# 12V_IdealDiode_PowerSupply_v1.net
KiCad netlist of a schematic drawn in Altium Designer
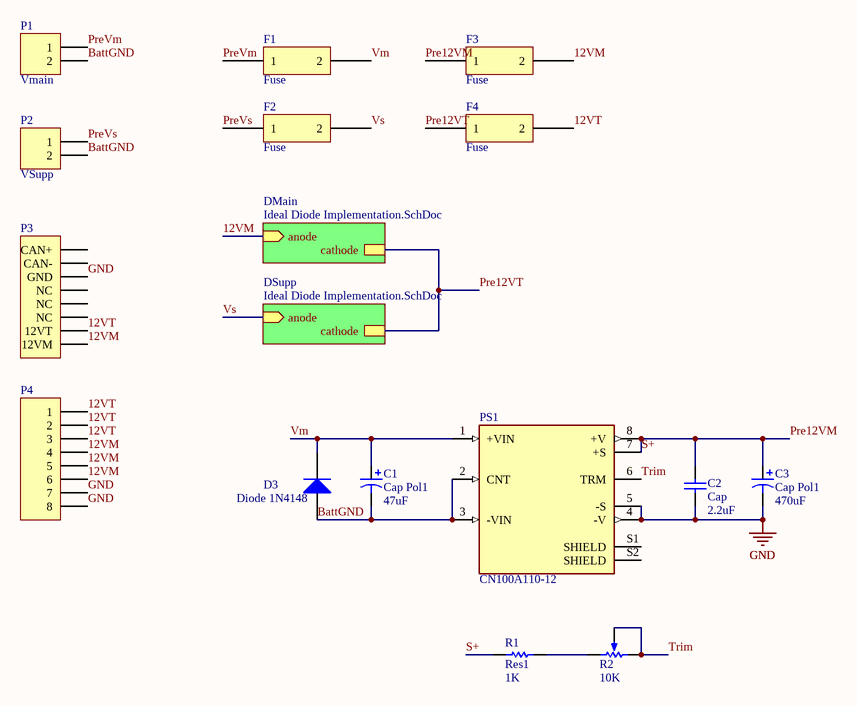
[diagram p0: 12V_IdealDiode_PowerSupply_v1.SchDoc]

(export (version "E")
  (design (tool "Eeschema 10.0.6"))
  (components
    (comp (ref "C1")
      (value "Cap Pol1")
      (footprint "RB7.6-15")
      (description "Polarized Capacitor (Radial)")
      (fields (field (name "ALTIUM_VALUE") "47uF") (field (name "PUBLISHER") "Altium Limited"))
      (libsource (lib "Miscellaneous Devices") (part "Cap Pol1"))
    )
    (comp (ref "C2")
      (value "Cap")
      (footprint "RAD-0.3")
      (description "Ceramic Capacitor")
      (fields (field (name "ALTIUM_VALUE") "2.2uF") (field (name "PUBLISHER") "Altium Limited"))
      (libsource (lib "Miscellaneous Devices") (part "Cap"))
    )
    (comp (ref "C3")
      (value "Cap Pol1")
      (footprint "RB7.6-15")
      (description "Polarized Capacitor (Radial)")
      (fields (field (name "ALTIUM_VALUE") "470uF") (field (name "PUBLISHER") "Altium Limited"))
      (libsource (lib "Miscellaneous Devices") (part "Cap Pol1"))
    )
    (comp (ref "D3")
      (value "Diode 1N4148")
      (footprint "DO-35")
      (description "High Conductance Fast Diode")
      (fields (field (name "PUBLISHER") "Altium Limited"))
      (libsource (lib "Miscellaneous Devices") (part "Diode 1N4148"))
    )
    (comp (ref "F1") (value "Fuse") (footprint "Fuse Hilder") (libsource (lib "SolarGators") (part "Fuse")))
    (comp (ref "F2") (value "Fuse") (footprint "Fuse Hilder") (libsource (lib "SolarGators") (part "Fuse")))
    (comp (ref "F3") (value "Fuse") (footprint "Fuse Hilder") (libsource (lib "SolarGators") (part "Fuse")))
    (comp (ref "F4") (value "Fuse") (footprint "Fuse Hilder") (libsource (lib "SolarGators") (part "Fuse")))
    (comp (ref "P1")
      (value "Vmain")
      (footprint "HDR1X2H")
      (description "Header, 2-Pin, Right Angle")
      (fields (field (name "PUBLISHER") "Altium Limited"))
      (libsource (lib "Miscellaneous Connectors") (part "Header 2H"))
    )
    (comp (ref "P2")
      (value "VSupp")
      (footprint "HDR1X2H")
      (description "Header, 2-Pin, Right Angle")
      (fields (field (name "PUBLISHER") "Altium Limited"))
      (libsource (lib "Miscellaneous Connectors") (part "Header 2H"))
    )
    (comp (ref "P3")
      (value "Header 8")
      (footprint "HDR1X8")
      (description "Header, 8-Pin")
      (fields (field (name "PUBLISHER") "Altium Limited"))
      (libsource (lib "Miscellaneous Connectors") (part "Header 8"))
    )
    (comp (ref "P4")
      (value "Header 8")
      (footprint "HDR1X8")
      (description "Header, 8-Pin")
      (fields (field (name "PUBLISHER") "Altium Limited"))
      (libsource (lib "Miscellaneous Connectors") (part "Header 8"))
    )
    (comp (ref "PS1")
      (value "CN100A110-12")
      (footprint "CONV_CN100A110-12")
      (description "Isolated Module DC DC Converter 1 Output 12V - - 8.4A 60V - 160V Input")
      (fields (field (name "MF") "TDK-Lambda Americas Inc"))
      (libsource (lib "CN100A110-12") (part "CN100A110-12"))
    )
    (comp (ref "R1")
      (value "Res1")
      (footprint "AXIAL-0.3")
      (description "Resistor")
      (fields (field (name "ALTIUM_VALUE") "1K") (field (name "PUBLISHER") "Altium Limited"))
      (libsource (lib "Miscellaneous Devices") (part "Res1"))
    )
    (comp (ref "R2")
      (value "10K")
      (footprint "POT OFFSET 100_1")
      (description "Potentiometer")
      (fields (field (name "Comment") "RPot_2") (field (name "PUBLISHER") "Altium Limited"))
      (libsource (lib "ECE LIB new") (part "RPot_5"))
    )
  )
  (nets
    (net (code "1") (name "/12VM") (class "Default")
      (node (ref "F3") (pin "2") (pinfunction "2_2") (pintype "passive"))
      (node (ref "P3") (pin "8") (pinfunction "8_8") (pintype "passive"))
      (node (ref "P4") (pin "4") (pinfunction "4_4") (pintype "passive"))
      (node (ref "P4") (pin "5") (pinfunction "5_5") (pintype "passive"))
      (node (ref "P4") (pin "6") (pinfunction "6_6") (pintype "passive"))
    )
    (net (code "2") (name "/12VT") (class "Default")
      (node (ref "F4") (pin "2") (pinfunction "2_2") (pintype "passive"))
      (node (ref "P3") (pin "7") (pinfunction "7_7") (pintype "passive"))
      (node (ref "P4") (pin "1") (pinfunction "1_1") (pintype "passive"))
      (node (ref "P4") (pin "2") (pinfunction "2_2") (pintype "passive"))
      (node (ref "P4") (pin "3") (pinfunction "3_3") (pintype "passive"))
    )
    (net (code "3") (name "/BattGND") (class "Default")
      (node (ref "C1") (pin "2") (pinfunction "2_2") (pintype "passive"))
      (node (ref "D3") (pin "1") (pinfunction "A_1") (pintype "passive"))
      (node (ref "P1") (pin "2") (pinfunction "2_2") (pintype "passive"))
      (node (ref "P2") (pin "2") (pinfunction "2_2") (pintype "passive"))
      (node (ref "PS1") (pin "2") (pinfunction "CNT_2") (pintype "input"))
      (node (ref "PS1") (pin "3") (pinfunction "-VIN_3") (pintype "input"))
    )
    (net (code "4") (name "/Pre12VM") (class "Default")
      (node (ref "C2") (pin "2") (pinfunction "2_2") (pintype "passive"))
      (node (ref "C3") (pin "1") (pinfunction "1_1") (pintype "passive"))
      (node (ref "F3") (pin "1") (pinfunction "1_1") (pintype "passive"))
      (node (ref "PS1") (pin "7") (pinfunction "+S_7") (pintype "passive"))
      (node (ref "PS1") (pin "8") (pinfunction "+V_8") (pintype "output"))
      (node (ref "R1") (pin "1") (pinfunction "1_1") (pintype "passive"))
    )
    (net (code "5") (name "/Pre12VT") (class "Default")
      (node (ref "F4") (pin "1") (pinfunction "1_1") (pintype "passive"))
    )
    (net (code "6") (name "/PreVm") (class "Default")
      (node (ref "F1") (pin "1") (pinfunction "1_1") (pintype "passive"))
      (node (ref "P1") (pin "1") (pinfunction "1_1") (pintype "passive"))
    )
    (net (code "7") (name "/PreVs") (class "Default")
      (node (ref "F2") (pin "1") (pinfunction "1_1") (pintype "passive"))
      (node (ref "P2") (pin "1") (pinfunction "1_1") (pintype "passive"))
    )
    (net (code "8") (name "/Trim") (class "Default")
      (node (ref "PS1") (pin "6") (pinfunction "TRM_6") (pintype "passive"))
      (node (ref "R2") (pin "1") (pinfunction "TOP_1") (pintype "passive"))
      (node (ref "R2") (pin "2") (pinfunction "TAP_2") (pintype "passive"))
    )
    (net (code "9") (name "/Vm") (class "Default")
      (node (ref "C1") (pin "1") (pinfunction "1_1") (pintype "passive"))
      (node (ref "D3") (pin "2") (pinfunction "K_2") (pintype "passive"))
      (node (ref "F1") (pin "2") (pinfunction "2_2") (pintype "passive"))
      (node (ref "PS1") (pin "1") (pinfunction "+VIN_1") (pintype "input"))
    )
    (net (code "10") (name "/Vs") (class "Default")
      (node (ref "F2") (pin "2") (pinfunction "2_2") (pintype "passive"))
    )
    (net (code "11") (name "GND") (class "Default")
      (node (ref "C2") (pin "1") (pinfunction "1_1") (pintype "passive"))
      (node (ref "C3") (pin "2") (pinfunction "2_2") (pintype "passive"))
      (node (ref "P3") (pin "3") (pinfunction "3_3") (pintype "passive"))
      (node (ref "P4") (pin "7") (pinfunction "7_7") (pintype "passive"))
      (node (ref "P4") (pin "8") (pinfunction "8_8") (pintype "passive"))
      (node (ref "PS1") (pin "4") (pinfunction "-V_4") (pintype "output"))
      (node (ref "PS1") (pin "5") (pinfunction "-S_5") (pintype "passive"))
    )
    (net (code "12") (name "Net-(R2-BOT)") (class "Default")
      (node (ref "R1") (pin "2") (pinfunction "2_2") (pintype "passive"))
      (node (ref "R2") (pin "3") (pinfunction "BOT_3") (pintype "passive"))
    )
    (net (code "13") (name "unconnected-(P3-Pad1)") (class "Default")
      (node (ref "P3") (pin "1") (pinfunction "1_1") (pintype "passive"))
    )
    (net (code "14") (name "unconnected-(P3-Pad2)") (class "Default")
      (node (ref "P3") (pin "2") (pinfunction "2_2") (pintype "passive"))
    )
    (net (code "15") (name "unconnected-(P3-Pad4)") (class "Default")
      (node (ref "P3") (pin "4") (pinfunction "4_4") (pintype "passive"))
    )
    (net (code "16") (name "unconnected-(P3-Pad5)") (class "Default")
      (node (ref "P3") (pin "5") (pinfunction "5_5") (pintype "passive"))
    )
    (net (code "17") (name "unconnected-(P3-Pad6)") (class "Default")
      (node (ref "P3") (pin "6") (pinfunction "6_6") (pintype "passive"))
    )
    (net (code "18") (name "unconnected-(PS1-SHIELD-PadS1)") (class "Default")
      (node (ref "PS1") (pin "S1") (pinfunction "SHIELD_S1") (pintype "passive"))
    )
    (net (code "19") (name "unconnected-(PS1-SHIELD-PadS2)") (class "Default")
      (node (ref "PS1") (pin "S2") (pinfunction "SHIELD_S2") (pintype "passive"))
    )
  )
)
